# axiom_beta_power_adapter_v0_1.net
KiCad netlist of a schematic drawn in EAGLE
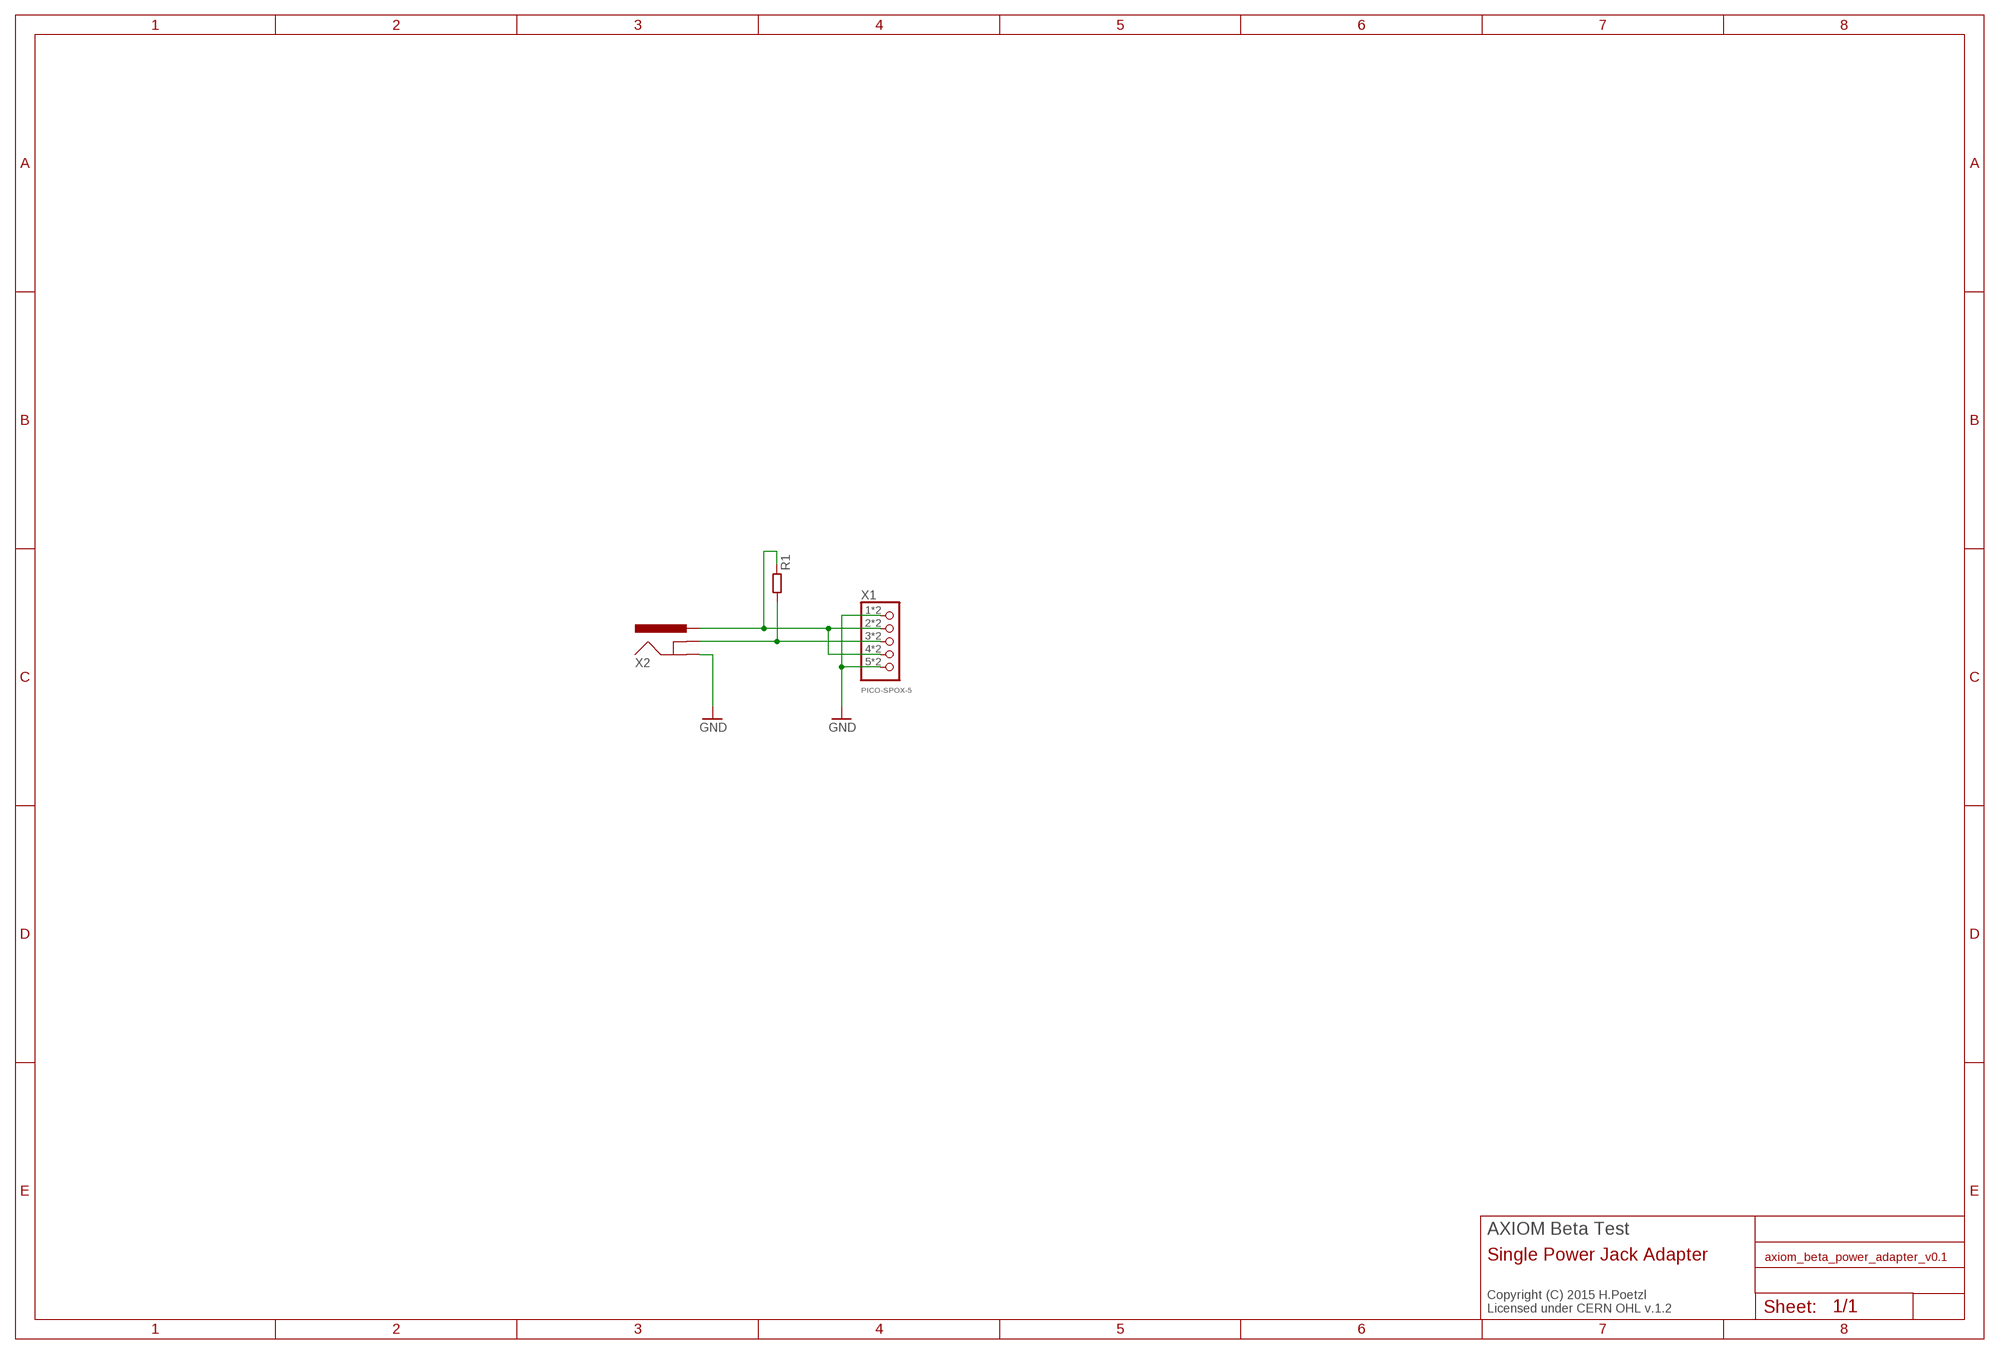
[diagram p0: schematic, sheet 1]

(export (version "E")
  (design (tool "Eeschema 10.0.6"))
  (components
    (comp (ref "R1")
      (value "R0402-B")
      (footprint "eagle-import:0402-B")
      (libsource (lib "eagle-import") (part "R0402-B"))
    )
    (comp (ref "X1")
      (value "PICO-SPOX-5")
      (footprint "eagle-import:PICO-SPOX-5")
      (libsource (lib "eagle-import") (part "PICO-SPOX-5"))
    )
    (comp (ref "X2")
      (value "POWER_JACKPTH")
      (footprint "eagle-import:POWER_JACK_PTH")
      (libsource (lib "eagle-import") (part "POWER_JACKPTH"))
    )
  )
  (nets
    (net (code "1") (name "GND") (class "Default")
      (node (ref "X1") (pin "1") (pinfunction "1_1") (pintype "passive"))
      (node (ref "X1") (pin "1A") (pinfunction "1_1A") (pintype "passive"))
      (node (ref "X1") (pin "5") (pinfunction "5_5") (pintype "passive"))
      (node (ref "X1") (pin "5A") (pinfunction "5_5A") (pintype "passive"))
      (node (ref "X2") (pin "GND") (pinfunction "GND_GND") (pintype "bidirectional"))
    )
    (net (code "2") (name "Net-(R1-Pad1)") (class "Default")
      (node (ref "R1") (pin "1") (pinfunction "1_1") (pintype "passive"))
      (node (ref "X1") (pin "2") (pinfunction "2_2") (pintype "passive"))
      (node (ref "X1") (pin "2A") (pinfunction "2_2A") (pintype "passive"))
      (node (ref "X1") (pin "4") (pinfunction "4_4") (pintype "passive"))
      (node (ref "X1") (pin "4A") (pinfunction "4_4A") (pintype "passive"))
      (node (ref "X2") (pin "PWR") (pinfunction "PWR_PWR") (pintype "bidirectional"))
    )
    (net (code "3") (name "Net-(X2-GNDBREAK)") (class "Default")
      (node (ref "R1") (pin "2") (pinfunction "2_2") (pintype "passive"))
      (node (ref "X1") (pin "3") (pinfunction "3_3") (pintype "passive"))
      (node (ref "X1") (pin "3A") (pinfunction "3_3A") (pintype "passive"))
      (node (ref "X2") (pin "SHUNT") (pinfunction "GNDBREAK_SHUNT") (pintype "bidirectional"))
    )
  )
)
